# Main.net
KiCad netlist of a schematic drawn in Altium Designer
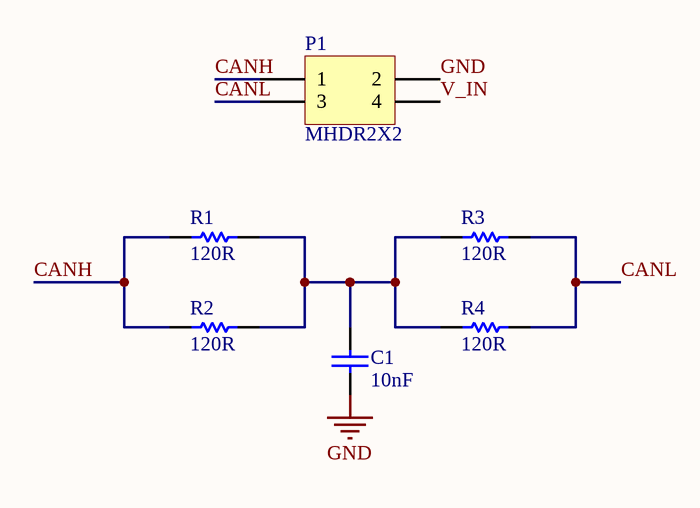
[diagram p0: Main.SchDoc]

(export (version "E")
  (design (tool "Eeschema 10.0.6"))
  (components
    (comp (ref "C1")
      (value "10nF")
      (footprint "CC0603")
      (description "0603 Capacitor")
      (fields (field (name "PART NUMBER") "10nF_CC0603"))
      (libsource (lib "ECE_Component_Library_2") (part "10nF_CC0603"))
    )
    (comp (ref "P1")
      (value "MHDR2X2")
      (footprint "MHDR2X2")
      (description "Header, 2-Pin, Dual row")
      (fields (field (name "PUBLISHER") "Altium Limited"))
      (libsource (lib "Miscellaneous Connectors") (part "MHDR2X2"))
    )
    (comp (ref "R1")
      (value "120R")
      (footprint "R0603")
      (description "0603 Resistor")
      (fields (field (name "PART NUMBER") "120R_R0603"))
      (libsource (lib "ECE_Component_Library_2") (part "120R_R0603"))
    )
    (comp (ref "R2")
      (value "120R")
      (footprint "R0603")
      (description "0603 Resistor")
      (fields (field (name "PART NUMBER") "120R_R0603"))
      (libsource (lib "ECE_Component_Library_2") (part "120R_R0603"))
    )
    (comp (ref "R3")
      (value "120R")
      (footprint "R0603")
      (description "0603 Resistor")
      (fields (field (name "PART NUMBER") "120R_R0603"))
      (libsource (lib "ECE_Component_Library_2") (part "120R_R0603"))
    )
    (comp (ref "R4")
      (value "120R")
      (footprint "R0603")
      (description "0603 Resistor")
      (fields (field (name "PART NUMBER") "120R_R0603"))
      (libsource (lib "ECE_Component_Library_2") (part "120R_R0603"))
    )
  )
  (nets
    (net (code "1") (name "/CANH") (class "Default")
      (node (ref "P1") (pin "1") (pinfunction "1_1") (pintype "passive"))
      (node (ref "R1") (pin "1") (pinfunction "1_1") (pintype "passive"))
      (node (ref "R2") (pin "1") (pinfunction "1_1") (pintype "passive"))
    )
    (net (code "2") (name "/CANL") (class "Default")
      (node (ref "P1") (pin "3") (pinfunction "3_3") (pintype "passive"))
      (node (ref "R3") (pin "2") (pinfunction "2_2") (pintype "passive"))
      (node (ref "R4") (pin "2") (pinfunction "2_2") (pintype "passive"))
    )
    (net (code "3") (name "/V_IN") (class "Default")
      (node (ref "P1") (pin "4") (pinfunction "4_4") (pintype "passive"))
    )
    (net (code "4") (name "GND") (class "Default")
      (node (ref "C1") (pin "1") (pinfunction "1_1") (pintype "passive"))
      (node (ref "P1") (pin "2") (pinfunction "2_2") (pintype "passive"))
    )
    (net (code "5") (name "Net-(C1-Pad2)") (class "Default")
      (node (ref "C1") (pin "2") (pinfunction "2_2") (pintype "passive"))
      (node (ref "R1") (pin "2") (pinfunction "2_2") (pintype "passive"))
      (node (ref "R2") (pin "2") (pinfunction "2_2") (pintype "passive"))
      (node (ref "R3") (pin "1") (pinfunction "1_1") (pintype "passive"))
      (node (ref "R4") (pin "1") (pinfunction "1_1") (pintype "passive"))
    )
  )
)
